# DINCONTROLLER.net
KiCad netlist of a schematic drawn in EAGLE
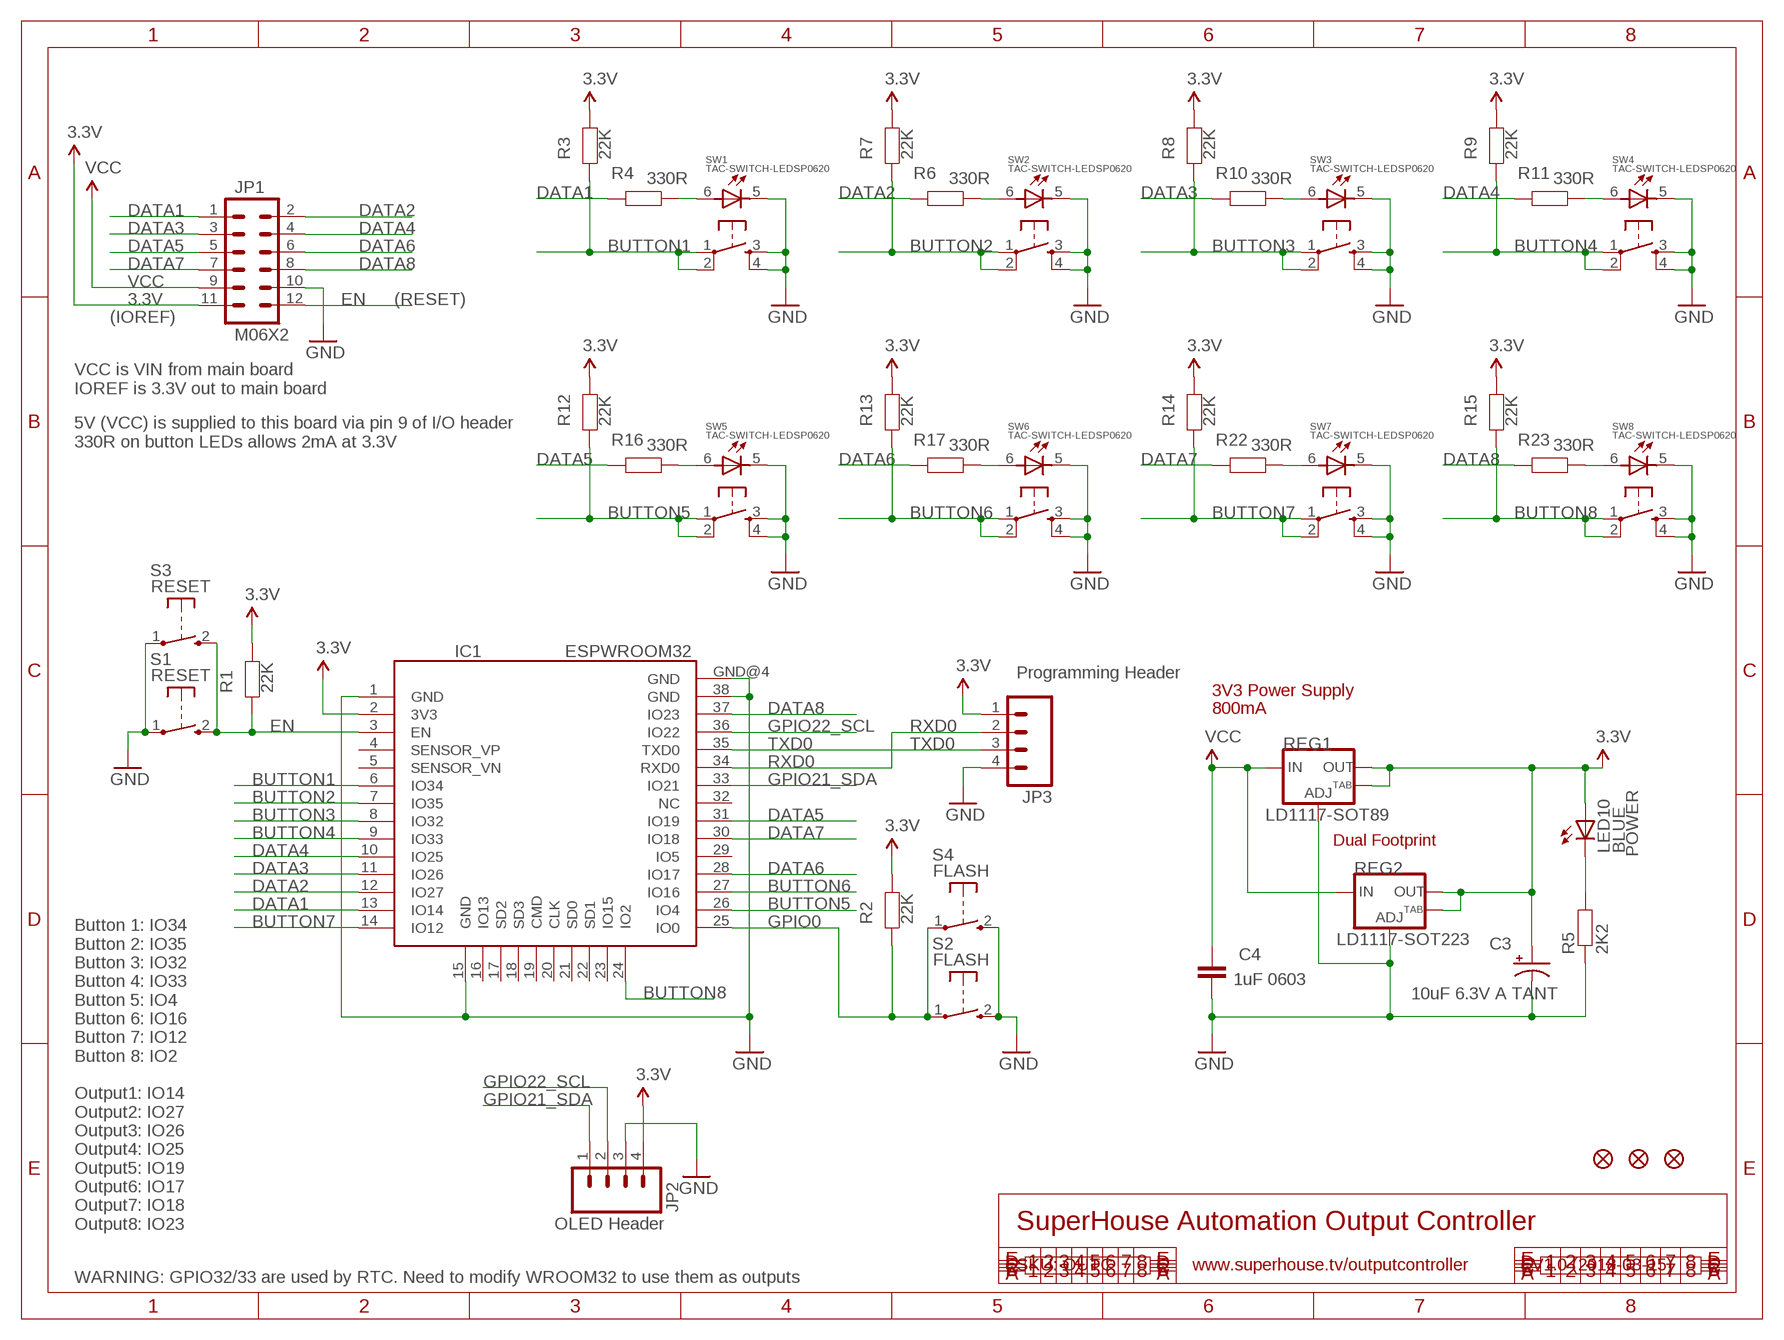
[diagram p0: schematic, sheet 1]

(export (version "E")
  (design (tool "Eeschema 10.0.6"))
  (components
    (comp (ref "C3")
      (value "10uF 6.3V A TANT")
      (footprint "eagle-import:EIA3216")
      (libsource (lib "eagle-import") (part "CAP_POL1206"))
    )
    (comp (ref "C4")
      (value "1uF 0603")
      (footprint "eagle-import:0603")
      (libsource (lib "eagle-import") (part "CAP0603"))
    )
    (comp (ref "FID1")
      (value "FIDUCIAL1X2.5")
      (footprint "eagle-import:FIDUCIAL-1X2.5")
      (libsource (lib "eagle-import") (part "FIDUCIAL1X2.5"))
    )
    (comp (ref "FID2")
      (value "FIDUCIAL1X2.5")
      (footprint "eagle-import:FIDUCIAL-1X2.5")
      (libsource (lib "eagle-import") (part "FIDUCIAL1X2.5"))
    )
    (comp (ref "FID3")
      (value "FIDUCIAL1X2.5")
      (footprint "eagle-import:FIDUCIAL-1X2.5")
      (libsource (lib "eagle-import") (part "FIDUCIAL1X2.5"))
    )
    (comp (ref "IC1")
      (value "ESPWROOM32")
      (footprint "eagle-import:ESPWROOM32")
      (libsource (lib "eagle-import") (part "ESPWROOM32"))
    )
    (comp (ref "JP1")
      (value "M06X2")
      (footprint "eagle-import:2X6-SHROUDED")
      (libsource (lib "eagle-import") (part "M06X2"))
    )
    (comp (ref "JP2")
      (value "M04PTH")
      (footprint "eagle-import:1X04")
      (libsource (lib "eagle-import") (part "M04PTH"))
    )
    (comp (ref "JP3")
      (value "M04PTH")
      (footprint "eagle-import:1X04")
      (libsource (lib "eagle-import") (part "M04PTH"))
    )
    (comp (ref "LED10")
      (value "BLUE")
      (footprint "eagle-import:LED3MM")
      (libsource (lib "eagle-import") (part "LED3MM"))
    )
    (comp (ref "R1")
      (value "22K")
      (footprint "eagle-import:0603@2")
      (libsource (lib "eagle-import") (part "RESISTOR0603"))
    )
    (comp (ref "R2")
      (value "22K")
      (footprint "eagle-import:0603@2")
      (libsource (lib "eagle-import") (part "RESISTOR0603"))
    )
    (comp (ref "R3")
      (value "22K")
      (footprint "eagle-import:0603@2")
      (libsource (lib "eagle-import") (part "RESISTOR0603"))
    )
    (comp (ref "R4")
      (value "330R")
      (footprint "eagle-import:0603@2")
      (libsource (lib "eagle-import") (part "RESISTOR0603"))
    )
    (comp (ref "R5")
      (value "2K2")
      (footprint "eagle-import:0603")
      (libsource (lib "eagle-import") (part "freetronics-jon_RESISTOR0603"))
    )
    (comp (ref "R6")
      (value "330R")
      (footprint "eagle-import:0603@2")
      (libsource (lib "eagle-import") (part "RESISTOR0603"))
    )
    (comp (ref "R7")
      (value "22K")
      (footprint "eagle-import:0603@2")
      (libsource (lib "eagle-import") (part "RESISTOR0603"))
    )
    (comp (ref "R8")
      (value "22K")
      (footprint "eagle-import:0603@2")
      (libsource (lib "eagle-import") (part "RESISTOR0603"))
    )
    (comp (ref "R9")
      (value "22K")
      (footprint "eagle-import:0603@2")
      (libsource (lib "eagle-import") (part "RESISTOR0603"))
    )
    (comp (ref "R10")
      (value "330R")
      (footprint "eagle-import:0603@2")
      (libsource (lib "eagle-import") (part "RESISTOR0603"))
    )
    (comp (ref "R11")
      (value "330R")
      (footprint "eagle-import:0603@2")
      (libsource (lib "eagle-import") (part "RESISTOR0603"))
    )
    (comp (ref "R12")
      (value "22K")
      (footprint "eagle-import:0603@2")
      (libsource (lib "eagle-import") (part "RESISTOR0603"))
    )
    (comp (ref "R13")
      (value "22K")
      (footprint "eagle-import:0603@2")
      (libsource (lib "eagle-import") (part "RESISTOR0603"))
    )
    (comp (ref "R14")
      (value "22K")
      (footprint "eagle-import:0603@2")
      (libsource (lib "eagle-import") (part "RESISTOR0603"))
    )
    (comp (ref "R15")
      (value "22K")
      (footprint "eagle-import:0603@2")
      (libsource (lib "eagle-import") (part "RESISTOR0603"))
    )
    (comp (ref "R16")
      (value "330R")
      (footprint "eagle-import:0603@2")
      (libsource (lib "eagle-import") (part "RESISTOR0603"))
    )
    (comp (ref "R17")
      (value "330R")
      (footprint "eagle-import:0603@2")
      (libsource (lib "eagle-import") (part "RESISTOR0603"))
    )
    (comp (ref "R22")
      (value "330R")
      (footprint "eagle-import:0603@2")
      (libsource (lib "eagle-import") (part "RESISTOR0603"))
    )
    (comp (ref "R23")
      (value "330R")
      (footprint "eagle-import:0603@2")
      (libsource (lib "eagle-import") (part "RESISTOR0603"))
    )
    (comp (ref "REG1")
      (value "LD1117-SOT89")
      (footprint "eagle-import:SOT89")
      (libsource (lib "eagle-import") (part "V_REG_LM1117SOT89"))
    )
    (comp (ref "REG2")
      (value "LD1117-SOT223")
      (footprint "eagle-import:SOT223")
      (libsource (lib "eagle-import") (part "V_REG_LM1117SOT223"))
    )
    (comp (ref "S1")
      (value "RESET")
      (footprint "eagle-import:TACTILE_SWITCH_SMD_2PIN_TINY")
      (libsource (lib "eagle-import") (part "TAC_SWITCH_2PINSMT"))
    )
    (comp (ref "S2")
      (value "FLASH")
      (footprint "eagle-import:TACTILE_SWITCH_SMD_2PIN_TINY")
      (libsource (lib "eagle-import") (part "TAC_SWITCH_2PINSMT"))
    )
    (comp (ref "S3")
      (value "RESET")
      (footprint "eagle-import:TACTILE_SWITCH_SMD_2PIN_TINY")
      (libsource (lib "eagle-import") (part "TAC_SWITCH_2PINSMT"))
    )
    (comp (ref "S4")
      (value "FLASH")
      (footprint "eagle-import:TACTILE_SWITCH_SMD_2PIN_TINY")
      (libsource (lib "eagle-import") (part "TAC_SWITCH_2PINSMT"))
    )
    (comp (ref "SW1")
      (value "TAC-SWITCH-LEDSP0620")
      (footprint "eagle-import:TACTILE-PTH-SP0620")
      (libsource (lib "eagle-import") (part "TAC-SWITCH-LEDSP0620"))
    )
    (comp (ref "SW2")
      (value "TAC-SWITCH-LEDSP0620")
      (footprint "eagle-import:TACTILE-PTH-SP0620")
      (libsource (lib "eagle-import") (part "TAC-SWITCH-LEDSP0620"))
    )
    (comp (ref "SW3")
      (value "TAC-SWITCH-LEDSP0620")
      (footprint "eagle-import:TACTILE-PTH-SP0620")
      (libsource (lib "eagle-import") (part "TAC-SWITCH-LEDSP0620"))
    )
    (comp (ref "SW4")
      (value "TAC-SWITCH-LEDSP0620")
      (footprint "eagle-import:TACTILE-PTH-SP0620")
      (libsource (lib "eagle-import") (part "TAC-SWITCH-LEDSP0620"))
    )
    (comp (ref "SW5")
      (value "TAC-SWITCH-LEDSP0620")
      (footprint "eagle-import:TACTILE-PTH-SP0620")
      (libsource (lib "eagle-import") (part "TAC-SWITCH-LEDSP0620"))
    )
    (comp (ref "SW6")
      (value "TAC-SWITCH-LEDSP0620")
      (footprint "eagle-import:TACTILE-PTH-SP0620")
      (libsource (lib "eagle-import") (part "TAC-SWITCH-LEDSP0620"))
    )
    (comp (ref "SW7")
      (value "TAC-SWITCH-LEDSP0620")
      (footprint "eagle-import:TACTILE-PTH-SP0620")
      (libsource (lib "eagle-import") (part "TAC-SWITCH-LEDSP0620"))
    )
    (comp (ref "SW8")
      (value "TAC-SWITCH-LEDSP0620")
      (footprint "eagle-import:TACTILE-PTH-SP0620")
      (libsource (lib "eagle-import") (part "TAC-SWITCH-LEDSP0620"))
    )
  )
  (nets
    (net (code "1") (name "/BUTTON1") (class "Default")
      (node (ref "IC1") (pin "6") (pinfunction "IO34_6") (pintype "bidirectional"))
      (node (ref "R3") (pin "2") (pinfunction "2_2") (pintype "passive"))
      (node (ref "SW1") (pin "1") (pinfunction "1_1") (pintype "passive"))
      (node (ref "SW1") (pin "2") (pinfunction "6_2") (pintype "passive"))
    )
    (net (code "2") (name "/BUTTON2") (class "Default")
      (node (ref "IC1") (pin "7") (pinfunction "IO35_7") (pintype "bidirectional"))
      (node (ref "R7") (pin "2") (pinfunction "2_2") (pintype "passive"))
      (node (ref "SW2") (pin "1") (pinfunction "1_1") (pintype "passive"))
      (node (ref "SW2") (pin "2") (pinfunction "6_2") (pintype "passive"))
    )
    (net (code "3") (name "/BUTTON3") (class "Default")
      (node (ref "IC1") (pin "8") (pinfunction "IO32_8") (pintype "bidirectional"))
      (node (ref "R8") (pin "2") (pinfunction "2_2") (pintype "passive"))
      (node (ref "SW3") (pin "1") (pinfunction "1_1") (pintype "passive"))
      (node (ref "SW3") (pin "2") (pinfunction "6_2") (pintype "passive"))
    )
    (net (code "4") (name "/BUTTON4") (class "Default")
      (node (ref "IC1") (pin "9") (pinfunction "IO33_9") (pintype "bidirectional"))
      (node (ref "R9") (pin "2") (pinfunction "2_2") (pintype "passive"))
      (node (ref "SW4") (pin "1") (pinfunction "1_1") (pintype "passive"))
      (node (ref "SW4") (pin "2") (pinfunction "6_2") (pintype "passive"))
    )
    (net (code "5") (name "/BUTTON5") (class "Default")
      (node (ref "IC1") (pin "26") (pinfunction "IO4_26") (pintype "bidirectional"))
      (node (ref "R12") (pin "2") (pinfunction "2_2") (pintype "passive"))
      (node (ref "SW5") (pin "1") (pinfunction "1_1") (pintype "passive"))
      (node (ref "SW5") (pin "2") (pinfunction "6_2") (pintype "passive"))
    )
    (net (code "6") (name "/BUTTON6") (class "Default")
      (node (ref "IC1") (pin "27") (pinfunction "IO16_27") (pintype "bidirectional"))
      (node (ref "R13") (pin "2") (pinfunction "2_2") (pintype "passive"))
      (node (ref "SW6") (pin "1") (pinfunction "1_1") (pintype "passive"))
      (node (ref "SW6") (pin "2") (pinfunction "6_2") (pintype "passive"))
    )
    (net (code "7") (name "/BUTTON7") (class "Default")
      (node (ref "IC1") (pin "14") (pinfunction "IO12_14") (pintype "bidirectional"))
      (node (ref "R14") (pin "2") (pinfunction "2_2") (pintype "passive"))
      (node (ref "SW7") (pin "1") (pinfunction "1_1") (pintype "passive"))
      (node (ref "SW7") (pin "2") (pinfunction "6_2") (pintype "passive"))
    )
    (net (code "8") (name "/BUTTON8") (class "Default")
      (node (ref "IC1") (pin "24") (pinfunction "IO2_24") (pintype "bidirectional"))
      (node (ref "R15") (pin "2") (pinfunction "2_2") (pintype "passive"))
      (node (ref "SW8") (pin "1") (pinfunction "1_1") (pintype "passive"))
      (node (ref "SW8") (pin "2") (pinfunction "6_2") (pintype "passive"))
    )
    (net (code "9") (name "/DATA1") (class "Default")
      (node (ref "IC1") (pin "13") (pinfunction "IO14_13") (pintype "bidirectional"))
      (node (ref "JP1") (pin "1") (pinfunction "1_1") (pintype "passive"))
      (node (ref "R4") (pin "2") (pinfunction "2_2") (pintype "passive"))
    )
    (net (code "10") (name "/DATA2") (class "Default")
      (node (ref "IC1") (pin "12") (pinfunction "IO27_12") (pintype "bidirectional"))
      (node (ref "JP1") (pin "2") (pinfunction "2_2") (pintype "passive"))
      (node (ref "R6") (pin "2") (pinfunction "2_2") (pintype "passive"))
    )
    (net (code "11") (name "/DATA3") (class "Default")
      (node (ref "IC1") (pin "11") (pinfunction "IO26_11") (pintype "bidirectional"))
      (node (ref "JP1") (pin "3") (pinfunction "3_3") (pintype "passive"))
      (node (ref "R10") (pin "2") (pinfunction "2_2") (pintype "passive"))
    )
    (net (code "12") (name "/DATA4") (class "Default")
      (node (ref "IC1") (pin "10") (pinfunction "IO25_10") (pintype "bidirectional"))
      (node (ref "JP1") (pin "4") (pinfunction "4_4") (pintype "passive"))
      (node (ref "R11") (pin "2") (pinfunction "2_2") (pintype "passive"))
    )
    (net (code "13") (name "/DATA5") (class "Default")
      (node (ref "IC1") (pin "31") (pinfunction "IO19_31") (pintype "bidirectional"))
      (node (ref "JP1") (pin "5") (pinfunction "5_5") (pintype "passive"))
      (node (ref "R16") (pin "2") (pinfunction "2_2") (pintype "passive"))
    )
    (net (code "14") (name "/DATA6") (class "Default")
      (node (ref "IC1") (pin "28") (pinfunction "IO17_28") (pintype "bidirectional"))
      (node (ref "JP1") (pin "6") (pinfunction "6_6") (pintype "passive"))
      (node (ref "R17") (pin "2") (pinfunction "2_2") (pintype "passive"))
    )
    (net (code "15") (name "/DATA7") (class "Default")
      (node (ref "IC1") (pin "30") (pinfunction "IO18_30") (pintype "bidirectional"))
      (node (ref "JP1") (pin "7") (pinfunction "7_7") (pintype "passive"))
      (node (ref "R22") (pin "2") (pinfunction "2_2") (pintype "passive"))
    )
    (net (code "16") (name "/DATA8") (class "Default")
      (node (ref "IC1") (pin "37") (pinfunction "IO23_37") (pintype "bidirectional"))
      (node (ref "JP1") (pin "8") (pinfunction "8_8") (pintype "passive"))
      (node (ref "R23") (pin "2") (pinfunction "2_2") (pintype "passive"))
    )
    (net (code "17") (name "/EN") (class "Default")
      (node (ref "IC1") (pin "3") (pinfunction "EN_3") (pintype "bidirectional"))
      (node (ref "JP1") (pin "12") (pinfunction "12_12") (pintype "passive"))
      (node (ref "R1") (pin "2") (pinfunction "2_2") (pintype "passive"))
      (node (ref "S1") (pin "2") (pinfunction "S_2") (pintype "passive"))
      (node (ref "S3") (pin "2") (pinfunction "S_2") (pintype "passive"))
    )
    (net (code "18") (name "/GPIO0") (class "Default")
      (node (ref "IC1") (pin "25") (pinfunction "IO0_25") (pintype "bidirectional"))
      (node (ref "R2") (pin "2") (pinfunction "2_2") (pintype "passive"))
      (node (ref "S2") (pin "1") (pinfunction "P_1") (pintype "passive"))
      (node (ref "S4") (pin "1") (pinfunction "P_1") (pintype "passive"))
    )
    (net (code "19") (name "/GPIO21_SDA") (class "Default")
      (node (ref "IC1") (pin "33") (pinfunction "IO21_33") (pintype "bidirectional"))
      (node (ref "JP2") (pin "1") (pinfunction "1_1") (pintype "passive"))
    )
    (net (code "20") (name "/GPIO22_SCL") (class "Default")
      (node (ref "IC1") (pin "36") (pinfunction "IO22_36") (pintype "bidirectional"))
      (node (ref "JP2") (pin "2") (pinfunction "2_2") (pintype "passive"))
    )
    (net (code "21") (name "/RXD0") (class "Default")
      (node (ref "IC1") (pin "34") (pinfunction "RXD0_34") (pintype "bidirectional"))
      (node (ref "JP3") (pin "2") (pinfunction "2_2") (pintype "passive"))
    )
    (net (code "22") (name "/TXD0") (class "Default")
      (node (ref "IC1") (pin "35") (pinfunction "TXD0_35") (pintype "bidirectional"))
      (node (ref "JP3") (pin "3") (pinfunction "3_3") (pintype "passive"))
    )
    (net (code "23") (name "3.3V") (class "Default")
      (node (ref "C3") (pin "A") (pinfunction "+_A") (pintype "passive"))
      (node (ref "IC1") (pin "2") (pinfunction "3V3_2") (pintype "power_in"))
      (node (ref "JP1") (pin "11") (pinfunction "11_11") (pintype "passive"))
      (node (ref "JP2") (pin "4") (pinfunction "4_4") (pintype "passive"))
      (node (ref "JP3") (pin "1") (pinfunction "1_1") (pintype "passive"))
      (node (ref "LED10") (pin "A") (pinfunction "A_A") (pintype "passive"))
      (node (ref "R1") (pin "1") (pinfunction "1_1") (pintype "passive"))
      (node (ref "R12") (pin "1") (pinfunction "1_1") (pintype "passive"))
      (node (ref "R13") (pin "1") (pinfunction "1_1") (pintype "passive"))
      (node (ref "R14") (pin "1") (pinfunction "1_1") (pintype "passive"))
      (node (ref "R15") (pin "1") (pinfunction "1_1") (pintype "passive"))
      (node (ref "R2") (pin "1") (pinfunction "1_1") (pintype "passive"))
      (node (ref "R3") (pin "1") (pinfunction "1_1") (pintype "passive"))
      (node (ref "R7") (pin "1") (pinfunction "1_1") (pintype "passive"))
      (node (ref "R8") (pin "1") (pinfunction "1_1") (pintype "passive"))
      (node (ref "R9") (pin "1") (pinfunction "1_1") (pintype "passive"))
      (node (ref "REG1") (pin "2") (pinfunction "OUT_2") (pintype "output"))
      (node (ref "REG1") (pin "4") (pinfunction "OUT_4") (pintype "output"))
      (node (ref "REG2") (pin "2") (pinfunction "OUT_2") (pintype "output"))
      (node (ref "REG2") (pin "4") (pinfunction "OUT_4") (pintype "output"))
    )
    (net (code "24") (name "GND") (class "Default")
      (node (ref "C3") (pin "C") (pinfunction "-_C") (pintype "passive"))
      (node (ref "C4") (pin "2") (pinfunction "2_2") (pintype "passive"))
      (node (ref "IC1") (pin "1") (pinfunction "GND_1") (pintype "power_in"))
      (node (ref "IC1") (pin "15") (pinfunction "GND_15") (pintype "power_in"))
      (node (ref "IC1") (pin "38") (pinfunction "GND_38") (pintype "power_in"))
      (node (ref "IC1") (pin "GND@4") (pinfunction "GND_GND@4") (pintype "power_in"))
      (node (ref "JP1") (pin "10") (pinfunction "10_10") (pintype "passive"))
      (node (ref "JP2") (pin "3") (pinfunction "3_3") (pintype "passive"))
      (node (ref "JP3") (pin "4") (pinfunction "4_4") (pintype "passive"))
      (node (ref "R5") (pin "1") (pinfunction "1_1") (pintype "passive"))
      (node (ref "REG1") (pin "1") (pinfunction "ADJ_1") (pintype "input"))
      (node (ref "REG2") (pin "1") (pinfunction "ADJ_1") (pintype "input"))
      (node (ref "S1") (pin "1") (pinfunction "P_1") (pintype "passive"))
      (node (ref "S2") (pin "2") (pinfunction "S_2") (pintype "passive"))
      (node (ref "S3") (pin "1") (pinfunction "P_1") (pintype "passive"))
      (node (ref "S4") (pin "2") (pinfunction "S_2") (pintype "passive"))
      (node (ref "SW1") (pin "3") (pinfunction "3_3") (pintype "passive"))
      (node (ref "SW1") (pin "4") (pinfunction "4_4") (pintype "passive"))
      (node (ref "SW1") (pin "5") (pinfunction "C_5") (pintype "passive"))
      (node (ref "SW2") (pin "3") (pinfunction "3_3") (pintype "passive"))
      (node (ref "SW2") (pin "4") (pinfunction "4_4") (pintype "passive"))
      (node (ref "SW2") (pin "5") (pinfunction "C_5") (pintype "passive"))
      (node (ref "SW3") (pin "3") (pinfunction "3_3") (pintype "passive"))
      (node (ref "SW3") (pin "4") (pinfunction "4_4") (pintype "passive"))
      (node (ref "SW3") (pin "5") (pinfunction "C_5") (pintype "passive"))
      (node (ref "SW4") (pin "3") (pinfunction "3_3") (pintype "passive"))
      (node (ref "SW4") (pin "4") (pinfunction "4_4") (pintype "passive"))
      (node (ref "SW4") (pin "5") (pinfunction "C_5") (pintype "passive"))
      (node (ref "SW5") (pin "3") (pinfunction "3_3") (pintype "passive"))
      (node (ref "SW5") (pin "4") (pinfunction "4_4") (pintype "passive"))
      (node (ref "SW5") (pin "5") (pinfunction "C_5") (pintype "passive"))
      (node (ref "SW6") (pin "3") (pinfunction "3_3") (pintype "passive"))
      (node (ref "SW6") (pin "4") (pinfunction "4_4") (pintype "passive"))
      (node (ref "SW6") (pin "5") (pinfunction "C_5") (pintype "passive"))
      (node (ref "SW7") (pin "3") (pinfunction "3_3") (pintype "passive"))
      (node (ref "SW7") (pin "4") (pinfunction "4_4") (pintype "passive"))
      (node (ref "SW7") (pin "5") (pinfunction "C_5") (pintype "passive"))
      (node (ref "SW8") (pin "3") (pinfunction "3_3") (pintype "passive"))
      (node (ref "SW8") (pin "4") (pinfunction "4_4") (pintype "passive"))
      (node (ref "SW8") (pin "5") (pinfunction "C_5") (pintype "passive"))
    )
    (net (code "25") (name "Net-(LED10-C)") (class "Default")
      (node (ref "LED10") (pin "K") (pinfunction "C_K") (pintype "passive"))
      (node (ref "R5") (pin "2") (pinfunction "2_2") (pintype "passive"))
    )
    (net (code "26") (name "Net-(SW1-A)") (class "Default")
      (node (ref "R4") (pin "1") (pinfunction "1_1") (pintype "passive"))
      (node (ref "SW1") (pin "6") (pinfunction "A_6") (pintype "passive"))
    )
    (net (code "27") (name "Net-(SW2-A)") (class "Default")
      (node (ref "R6") (pin "1") (pinfunction "1_1") (pintype "passive"))
      (node (ref "SW2") (pin "6") (pinfunction "A_6") (pintype "passive"))
    )
    (net (code "28") (name "Net-(SW3-A)") (class "Default")
      (node (ref "R10") (pin "1") (pinfunction "1_1") (pintype "passive"))
      (node (ref "SW3") (pin "6") (pinfunction "A_6") (pintype "passive"))
    )
    (net (code "29") (name "Net-(SW4-A)") (class "Default")
      (node (ref "R11") (pin "1") (pinfunction "1_1") (pintype "passive"))
      (node (ref "SW4") (pin "6") (pinfunction "A_6") (pintype "passive"))
    )
    (net (code "30") (name "Net-(SW5-A)") (class "Default")
      (node (ref "R16") (pin "1") (pinfunction "1_1") (pintype "passive"))
      (node (ref "SW5") (pin "6") (pinfunction "A_6") (pintype "passive"))
    )
    (net (code "31") (name "Net-(SW6-A)") (class "Default")
      (node (ref "R17") (pin "1") (pinfunction "1_1") (pintype "passive"))
      (node (ref "SW6") (pin "6") (pinfunction "A_6") (pintype "passive"))
    )
    (net (code "32") (name "Net-(SW7-A)") (class "Default")
      (node (ref "R22") (pin "1") (pinfunction "1_1") (pintype "passive"))
      (node (ref "SW7") (pin "6") (pinfunction "A_6") (pintype "passive"))
    )
    (net (code "33") (name "Net-(SW8-A)") (class "Default")
      (node (ref "R23") (pin "1") (pinfunction "1_1") (pintype "passive"))
      (node (ref "SW8") (pin "6") (pinfunction "A_6") (pintype "passive"))
    )
    (net (code "34") (name "VCC") (class "Default")
      (node (ref "C4") (pin "1") (pinfunction "1_1") (pintype "passive"))
      (node (ref "JP1") (pin "9") (pinfunction "9_9") (pintype "passive"))
      (node (ref "REG1") (pin "3") (pinfunction "IN_3") (pintype "input"))
      (node (ref "REG2") (pin "3") (pinfunction "IN_3") (pintype "input"))
    )
    (net (code "35") (name "unconnected-(IC1-CLK-Pad20)") (class "Default")
      (node (ref "IC1") (pin "20") (pinfunction "CLK_20") (pintype "bidirectional"))
    )
    (net (code "36") (name "unconnected-(IC1-CMD-Pad19)") (class "Default")
      (node (ref "IC1") (pin "19") (pinfunction "CMD_19") (pintype "bidirectional"))
    )
    (net (code "37") (name "unconnected-(IC1-IO5-Pad29)") (class "Default")
      (node (ref "IC1") (pin "29") (pinfunction "IO5_29") (pintype "bidirectional"))
    )
    (net (code "38") (name "unconnected-(IC1-IO13-Pad16)") (class "Default")
      (node (ref "IC1") (pin "16") (pinfunction "IO13_16") (pintype "bidirectional"))
    )
    (net (code "39") (name "unconnected-(IC1-IO15-Pad23)") (class "Default")
      (node (ref "IC1") (pin "23") (pinfunction "IO15_23") (pintype "bidirectional"))
    )
    (net (code "40") (name "unconnected-(IC1-NC-Pad32)") (class "Default")
      (node (ref "IC1") (pin "32") (pinfunction "NC_32") (pintype "bidirectional"))
    )
    (net (code "41") (name "unconnected-(IC1-SD0-Pad21)") (class "Default")
      (node (ref "IC1") (pin "21") (pinfunction "SD0_21") (pintype "bidirectional"))
    )
    (net (code "42") (name "unconnected-(IC1-SD1-Pad22)") (class "Default")
      (node (ref "IC1") (pin "22") (pinfunction "SD1_22") (pintype "bidirectional"))
    )
    (net (code "43") (name "unconnected-(IC1-SD2-Pad17)") (class "Default")
      (node (ref "IC1") (pin "17") (pinfunction "SD2_17") (pintype "bidirectional"))
    )
    (net (code "44") (name "unconnected-(IC1-SD3-Pad18)") (class "Default")
      (node (ref "IC1") (pin "18") (pinfunction "SD3_18") (pintype "bidirectional"))
    )
    (net (code "45") (name "unconnected-(IC1-SENSOR_VN-Pad5)") (class "Default")
      (node (ref "IC1") (pin "5") (pinfunction "SENSOR_VN_5") (pintype "bidirectional"))
    )
    (net (code "46") (name "unconnected-(IC1-SENSOR_VP-Pad4)") (class "Default")
      (node (ref "IC1") (pin "4") (pinfunction "SENSOR_VP_4") (pintype "bidirectional"))
    )
  )
)
